# IMU.net
KiCad netlist of a schematic drawn in Altium Designer
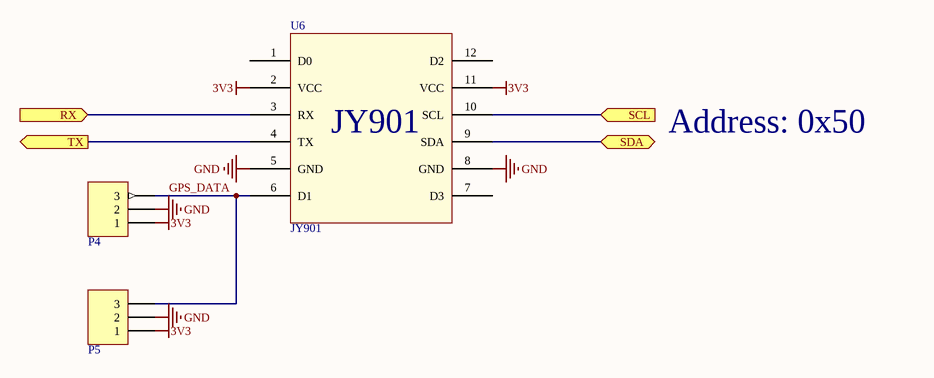
[diagram p0: IMU.SchDoc]

(export (version "E")
  (design (tool "Eeschema 10.0.6"))
  (components
    (comp (ref "P4")
      (value "0.1\" 3POS Header SNGL")
      (footprint "3 POS HEADER SINGLE ROW")
      (description "CONN HEADER 3POS .100\" SNGL TIN")
      (fields
        (field (name "MANUFACTURER") "Samtec Inc")
        (field (name "MANUFACTURER PART NUMBER") "TSW-150-08-T-S")
      )
      (libsource (lib "") (part "Header 3_1"))
    )
    (comp (ref "P5")
      (value "B3B-PH-SM4-TB(LF)(SN)")
      (footprint "B3B-PH-SM4-TB(LF)(SN)")
      (description "CONN HEADER PH TOP 3POS 2MM SMD")
      (fields (field (name "MANUFACTURER") "JST Sales America Inc."))
      (libsource (lib "RoboteX") (part "Header 3"))
    )
    (comp (ref "U6") (value "JY901") (footprint "JY-901") (libsource (lib "lib") (part "JY901")))
  )
  (nets
    (net (code "1") (name "/GPS_DATA") (class "Default")
      (node (ref "P4") (pin "3") (pinfunction "3_3") (pintype "output"))
      (node (ref "P5") (pin "3") (pinfunction "3_3") (pintype "passive"))
      (node (ref "U6") (pin "6") (pinfunction "D1_6") (pintype "passive"))
    )
    (net (code "2") (name "/RX") (class "Default")
      (node (ref "U6") (pin "3") (pinfunction "RX_3") (pintype "passive"))
    )
    (net (code "3") (name "/SCL") (class "Default")
      (node (ref "U6") (pin "10") (pinfunction "SCL_10") (pintype "passive"))
    )
    (net (code "4") (name "/SDA") (class "Default")
      (node (ref "U6") (pin "9") (pinfunction "SDA_9") (pintype "passive"))
    )
    (net (code "5") (name "/TX") (class "Default")
      (node (ref "U6") (pin "4") (pinfunction "TX_4") (pintype "passive"))
    )
    (net (code "6") (name "3V3") (class "Default")
      (node (ref "P4") (pin "1") (pinfunction "1_1") (pintype "passive"))
      (node (ref "P5") (pin "1") (pinfunction "1_1") (pintype "passive"))
      (node (ref "U6") (pin "11") (pinfunction "VCC_11") (pintype "passive"))
      (node (ref "U6") (pin "2") (pinfunction "VCC_2") (pintype "passive"))
    )
    (net (code "7") (name "GND") (class "Default")
      (node (ref "P4") (pin "2") (pinfunction "2_2") (pintype "passive"))
      (node (ref "P5") (pin "2") (pinfunction "2_2") (pintype "passive"))
      (node (ref "U6") (pin "5") (pinfunction "GND_5") (pintype "passive"))
      (node (ref "U6") (pin "8") (pinfunction "GND_8") (pintype "passive"))
    )
    (net (code "8") (name "unconnected-(U6-D0-Pad1)") (class "Default")
      (node (ref "U6") (pin "1") (pinfunction "D0_1") (pintype "passive"))
    )
    (net (code "9") (name "unconnected-(U6-D2-Pad12)") (class "Default")
      (node (ref "U6") (pin "12") (pinfunction "D2_12") (pintype "passive"))
    )
    (net (code "10") (name "unconnected-(U6-D3-Pad7)") (class "Default")
      (node (ref "U6") (pin "7") (pinfunction "D3_7") (pintype "passive"))
    )
  )
)
